# Indication.net
KiCad netlist of a schematic drawn in Altium Designer
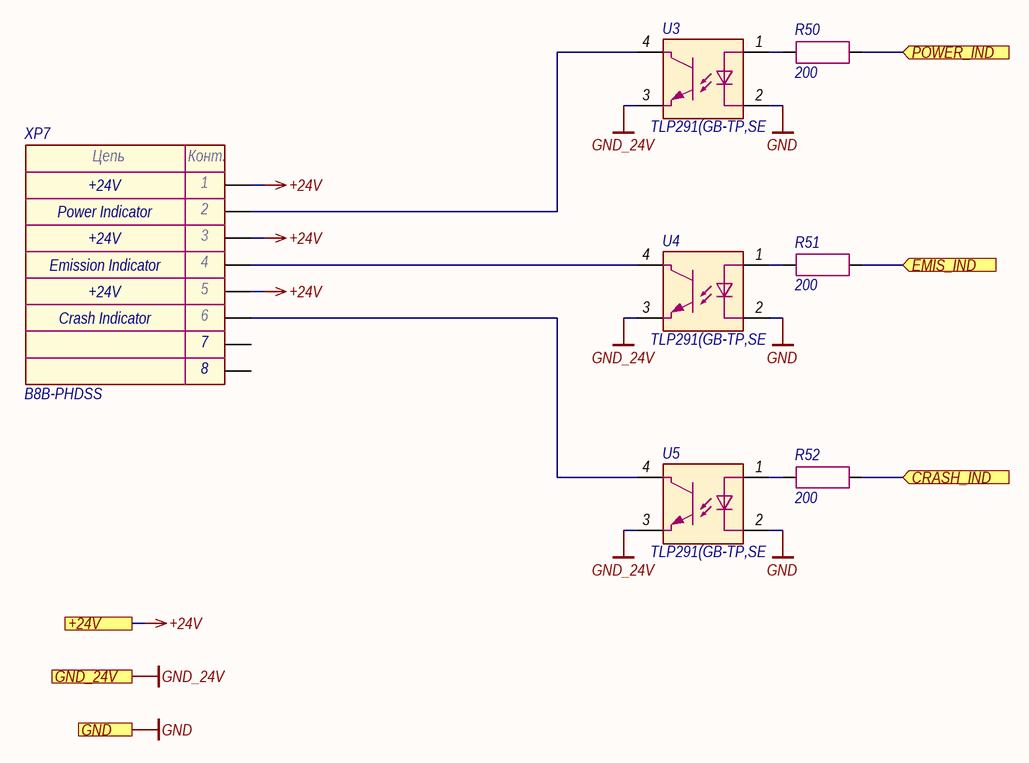
[diagram p0: Indication.SchDoc]

(export (version "E")
  (design (tool "Eeschema 10.0.6"))
  (components
    (comp (ref "R50")
      (value "200")
      (footprint "Pcb_library:RES_0603")
      (fields (field (name "MANUFACTURER") "Yageo"))
      (libsource (lib "Schem_library") (part "Resistor"))
    )
    (comp (ref "R51")
      (value "200")
      (footprint "Pcb_library:RES_0603")
      (fields (field (name "MANUFACTURER") "Yageo"))
      (libsource (lib "Schem_library") (part "Resistor"))
    )
    (comp (ref "R52")
      (value "200")
      (footprint "Pcb_library:RES_0603")
      (fields (field (name "MANUFACTURER") "Yageo"))
      (libsource (lib "Schem_library") (part "Resistor"))
    )
    (comp (ref "U3")
      (value "TLP291(GB-TP,SE")
      (footprint "Pcb_library:11-3C1")
      (fields (field (name "MANUFACTURER") "Toshiba"))
      (libsource (lib "Schem_library") (part "TLP291"))
    )
    (comp (ref "U4")
      (value "TLP291(GB-TP,SE")
      (footprint "Pcb_library:11-3C1")
      (fields (field (name "MANUFACTURER") "Toshiba"))
      (libsource (lib "Schem_library") (part "TLP291"))
    )
    (comp (ref "U5")
      (value "TLP291(GB-TP,SE")
      (footprint "Pcb_library:11-3C1")
      (fields (field (name "MANUFACTURER") "Toshiba"))
      (libsource (lib "Schem_library") (part "TLP291"))
    )
    (comp (ref "XP7")
      (value "B8B-PHDSS")
      (footprint "Pcb_library:B8B-PHDSS")
      (fields (field (name "MANUFACTURER") "JST"))
      (libsource (lib "Schem_library") (part "Connector-8"))
    )
  )
  (nets
    (net (code "1") (name "+24V") (class "Default")
      (node (ref "XP7") (pin "1") (pintype "passive"))
      (node (ref "XP7") (pin "3") (pintype "passive"))
      (node (ref "XP7") (pin "5") (pintype "passive"))
    )
    (net (code "2") (name "/CRASH_IND") (class "Default")
      (node (ref "R52") (pin "2") (pinfunction "2_2") (pintype "passive"))
    )
    (net (code "3") (name "/EMIS_IND") (class "Default")
      (node (ref "R51") (pin "2") (pinfunction "2_2") (pintype "passive"))
    )
    (net (code "4") (name "/POWER_IND") (class "Default")
      (node (ref "R50") (pin "2") (pinfunction "2_2") (pintype "passive"))
    )
    (net (code "5") (name "GND") (class "Default")
      (node (ref "U3") (pin "2") (pintype "passive"))
      (node (ref "U4") (pin "2") (pintype "passive"))
      (node (ref "U5") (pin "2") (pintype "passive"))
    )
    (net (code "6") (name "GND_24V") (class "Default")
      (node (ref "U3") (pin "3") (pintype "passive"))
      (node (ref "U4") (pin "3") (pintype "passive"))
      (node (ref "U5") (pin "3") (pintype "passive"))
    )
    (net (code "7") (name "Net-(R50-Pad1)") (class "Default")
      (node (ref "R50") (pin "1") (pinfunction "1_1") (pintype "passive"))
      (node (ref "U3") (pin "1") (pintype "passive"))
    )
    (net (code "8") (name "Net-(R51-Pad1)") (class "Default")
      (node (ref "R51") (pin "1") (pinfunction "1_1") (pintype "passive"))
      (node (ref "U4") (pin "1") (pintype "passive"))
    )
    (net (code "9") (name "Net-(R52-Pad1)") (class "Default")
      (node (ref "R52") (pin "1") (pinfunction "1_1") (pintype "passive"))
      (node (ref "U5") (pin "1") (pintype "passive"))
    )
    (net (code "10") (name "Net-(U3-Pad4)") (class "Default")
      (node (ref "U3") (pin "4") (pintype "passive"))
      (node (ref "XP7") (pin "2") (pintype "passive"))
    )
    (net (code "11") (name "Net-(U4-Pad4)") (class "Default")
      (node (ref "U4") (pin "4") (pintype "passive"))
      (node (ref "XP7") (pin "4") (pintype "passive"))
    )
    (net (code "12") (name "Net-(U5-Pad4)") (class "Default")
      (node (ref "U5") (pin "4") (pintype "passive"))
      (node (ref "XP7") (pin "6") (pintype "passive"))
    )
    (net (code "13") (name "unconnected-(XP7-Pad7)") (class "Default")
      (node (ref "XP7") (pin "7") (pintype "passive"))
    )
    (net (code "14") (name "unconnected-(XP7-Pad8)") (class "Default")
      (node (ref "XP7") (pin "8") (pintype "passive"))
    )
  )
)
